# M5R_I2C_MUX.net
KiCad netlist of a schematic drawn in EAGLE
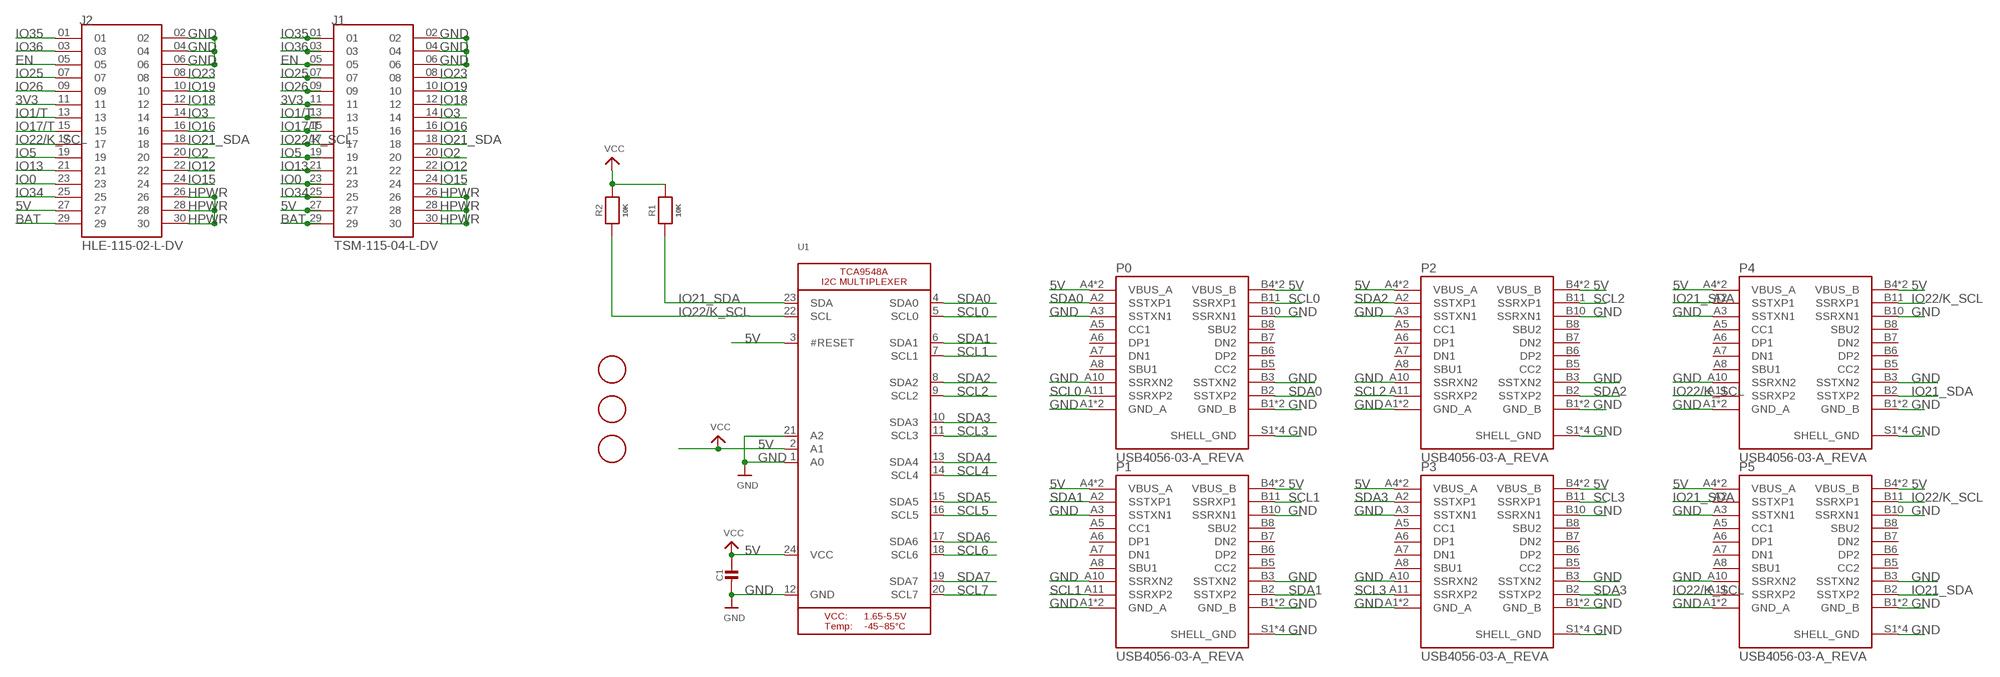
[diagram p0: schematic, sheet 1]

(export (version "E")
  (design (tool "Eeschema 10.0.6"))
  (components
    (comp (ref "C1")
      (value "CAP_CERAMIC0805-NOOUTLINE")
      (footprint "eagle-import:0805-NO")
      (libsource (lib "eagle-import") (part "CAP_CERAMIC0805-NOOUTLINE"))
    )
    (comp (ref "J1")
      (value "TSM-115-04-L-DV")
      (footprint "eagle-import:SAMTEC_TSM-115-04-L-DV")
      (fields (field (name "MF") "Samtec"))
      (libsource (lib "eagle-import") (part "TSM-115-04-L-DV"))
    )
    (comp (ref "J2")
      (value "HLE-115-02-L-DV")
      (footprint "eagle-import:SAMTEC_HLE-115-02-L-DV")
      (fields (field (name "MANUFACTURER") "Samtec Inc."))
      (libsource (lib "eagle-import") (part "HLE-115-02-L-DV"))
    )
    (comp (ref "P0")
      (value "USB4056-03-A_REVA")
      (footprint "eagle-import:GCT_USB4056-03-A_REVA")
      (fields (field (name "MANUFACTURER") "GCT"))
      (libsource (lib "eagle-import") (part "USB4056-03-A_REVA"))
    )
    (comp (ref "P1")
      (value "USB4056-03-A_REVA")
      (footprint "eagle-import:GCT_USB4056-03-A_REVA")
      (fields (field (name "MANUFACTURER") "GCT"))
      (libsource (lib "eagle-import") (part "USB4056-03-A_REVA"))
    )
    (comp (ref "P2")
      (value "USB4056-03-A_REVA")
      (footprint "eagle-import:GCT_USB4056-03-A_REVA")
      (fields (field (name "MANUFACTURER") "GCT"))
      (libsource (lib "eagle-import") (part "USB4056-03-A_REVA"))
    )
    (comp (ref "P3")
      (value "USB4056-03-A_REVA")
      (footprint "eagle-import:GCT_USB4056-03-A_REVA")
      (fields (field (name "MANUFACTURER") "GCT"))
      (libsource (lib "eagle-import") (part "USB4056-03-A_REVA"))
    )
    (comp (ref "P4")
      (value "USB4056-03-A_REVA")
      (footprint "eagle-import:GCT_USB4056-03-A_REVA")
      (fields (field (name "MANUFACTURER") "GCT"))
      (libsource (lib "eagle-import") (part "USB4056-03-A_REVA"))
    )
    (comp (ref "P5")
      (value "USB4056-03-A_REVA")
      (footprint "eagle-import:GCT_USB4056-03-A_REVA")
      (fields (field (name "MANUFACTURER") "GCT"))
      (libsource (lib "eagle-import") (part "USB4056-03-A_REVA"))
    )
    (comp (ref "R1")
      (value "10K")
      (footprint "eagle-import:0805")
      (libsource (lib "eagle-import") (part "RESISTOR_0805"))
    )
    (comp (ref "R2")
      (value "10K")
      (footprint "eagle-import:0805")
      (libsource (lib "eagle-import") (part "RESISTOR_0805"))
    )
    (comp (ref "U$3")
      (value "FIDUCIAL")
      (footprint "eagle-import:FIDUCIAL_1MM")
      (libsource (lib "eagle-import") (part "FIDUCIAL"))
    )
    (comp (ref "U$4")
      (value "FIDUCIAL")
      (footprint "eagle-import:FIDUCIAL_1MM")
      (libsource (lib "eagle-import") (part "FIDUCIAL"))
    )
    (comp (ref "U$5")
      (value "FIDUCIAL")
      (footprint "eagle-import:FIDUCIAL_1MM")
      (libsource (lib "eagle-import") (part "FIDUCIAL"))
    )
    (comp (ref "U1")
      (value "TCA9548A")
      (footprint "eagle-import:TSSOP24")
      (libsource (lib "eagle-import") (part "TCA9548A"))
    )
  )
  (nets
    (net (code "1") (name "/3V3") (class "Default")
      (node (ref "J1") (pin "11") (pinfunction "11_11") (pintype "passive"))
      (node (ref "J2") (pin "11") (pinfunction "11_11") (pintype "passive"))
    )
    (net (code "2") (name "/BAT") (class "Default")
      (node (ref "J1") (pin "29") (pinfunction "29_29") (pintype "passive"))
      (node (ref "J2") (pin "29") (pinfunction "29_29") (pintype "passive"))
    )
    (net (code "3") (name "/EN") (class "Default")
      (node (ref "J1") (pin "05") (pinfunction "05_05") (pintype "passive"))
      (node (ref "J2") (pin "05") (pinfunction "05_05") (pintype "passive"))
    )
    (net (code "4") (name "/HPWR") (class "Default")
      (node (ref "J1") (pin "26") (pinfunction "26_26") (pintype "passive"))
      (node (ref "J1") (pin "28") (pinfunction "28_28") (pintype "passive"))
      (node (ref "J1") (pin "30") (pinfunction "30_30") (pintype "passive"))
      (node (ref "J2") (pin "26") (pinfunction "26_26") (pintype "passive"))
      (node (ref "J2") (pin "28") (pinfunction "28_28") (pintype "passive"))
      (node (ref "J2") (pin "30") (pinfunction "30_30") (pintype "passive"))
    )
    (net (code "5") (name "/IO0") (class "Default")
      (node (ref "J1") (pin "23") (pinfunction "23_23") (pintype "passive"))
      (node (ref "J2") (pin "23") (pinfunction "23_23") (pintype "passive"))
    )
    (net (code "6") (name "/IO1{slash}T") (class "Default")
      (node (ref "J1") (pin "13") (pinfunction "13_13") (pintype "passive"))
      (node (ref "J2") (pin "13") (pinfunction "13_13") (pintype "passive"))
    )
    (net (code "7") (name "/IO2") (class "Default")
      (node (ref "J1") (pin "20") (pinfunction "20_20") (pintype "passive"))
      (node (ref "J2") (pin "20") (pinfunction "20_20") (pintype "passive"))
    )
    (net (code "8") (name "/IO3") (class "Default")
      (node (ref "J1") (pin "14") (pinfunction "14_14") (pintype "passive"))
      (node (ref "J2") (pin "14") (pinfunction "14_14") (pintype "passive"))
    )
    (net (code "9") (name "/IO5") (class "Default")
      (node (ref "J1") (pin "19") (pinfunction "19_19") (pintype "passive"))
      (node (ref "J2") (pin "19") (pinfunction "19_19") (pintype "passive"))
    )
    (net (code "10") (name "/IO12") (class "Default")
      (node (ref "J1") (pin "22") (pinfunction "22_22") (pintype "passive"))
      (node (ref "J2") (pin "22") (pinfunction "22_22") (pintype "passive"))
    )
    (net (code "11") (name "/IO13") (class "Default")
      (node (ref "J1") (pin "21") (pinfunction "21_21") (pintype "passive"))
      (node (ref "J2") (pin "21") (pinfunction "21_21") (pintype "passive"))
    )
    (net (code "12") (name "/IO15") (class "Default")
      (node (ref "J1") (pin "24") (pinfunction "24_24") (pintype "passive"))
      (node (ref "J2") (pin "24") (pinfunction "24_24") (pintype "passive"))
    )
    (net (code "13") (name "/IO16") (class "Default")
      (node (ref "J1") (pin "16") (pinfunction "16_16") (pintype "passive"))
      (node (ref "J2") (pin "16") (pinfunction "16_16") (pintype "passive"))
    )
    (net (code "14") (name "/IO17{slash}T") (class "Default")
      (node (ref "J1") (pin "15") (pinfunction "15_15") (pintype "passive"))
      (node (ref "J2") (pin "15") (pinfunction "15_15") (pintype "passive"))
    )
    (net (code "15") (name "/IO18") (class "Default")
      (node (ref "J1") (pin "12") (pinfunction "12_12") (pintype "passive"))
      (node (ref "J2") (pin "12") (pinfunction "12_12") (pintype "passive"))
    )
    (net (code "16") (name "/IO19") (class "Default")
      (node (ref "J1") (pin "10") (pinfunction "10_10") (pintype "passive"))
      (node (ref "J2") (pin "10") (pinfunction "10_10") (pintype "passive"))
    )
    (net (code "17") (name "/IO21_SDA") (class "Default")
      (node (ref "J1") (pin "18") (pinfunction "18_18") (pintype "passive"))
      (node (ref "J2") (pin "18") (pinfunction "18_18") (pintype "passive"))
      (node (ref "P4") (pin "A2") (pinfunction "SSTXP1_A2") (pintype "bidirectional"))
      (node (ref "P4") (pin "B2") (pinfunction "SSTXP2_B2") (pintype "bidirectional"))
      (node (ref "P5") (pin "A2") (pinfunction "SSTXP1_A2") (pintype "bidirectional"))
      (node (ref "P5") (pin "B2") (pinfunction "SSTXP2_B2") (pintype "bidirectional"))
      (node (ref "R1") (pin "1") (pinfunction "1_1") (pintype "passive"))
      (node (ref "U1") (pin "23") (pinfunction "SDA_23") (pintype "bidirectional"))
    )
    (net (code "18") (name "/IO22{slash}K_SCL") (class "Default")
      (node (ref "J1") (pin "17") (pinfunction "17_17") (pintype "passive"))
      (node (ref "J2") (pin "17") (pinfunction "17_17") (pintype "passive"))
      (node (ref "P4") (pin "A11") (pinfunction "SSRXP2_A11") (pintype "bidirectional"))
      (node (ref "P4") (pin "B11") (pinfunction "SSRXP1_B11") (pintype "bidirectional"))
      (node (ref "P5") (pin "A11") (pinfunction "SSRXP2_A11") (pintype "bidirectional"))
      (node (ref "P5") (pin "B11") (pinfunction "SSRXP1_B11") (pintype "bidirectional"))
      (node (ref "R2") (pin "1") (pinfunction "1_1") (pintype "passive"))
      (node (ref "U1") (pin "22") (pinfunction "SCL_22") (pintype "bidirectional"))
    )
    (net (code "19") (name "/IO23") (class "Default")
      (node (ref "J1") (pin "08") (pinfunction "08_08") (pintype "passive"))
      (node (ref "J2") (pin "08") (pinfunction "08_08") (pintype "passive"))
    )
    (net (code "20") (name "/IO25") (class "Default")
      (node (ref "J1") (pin "07") (pinfunction "07_07") (pintype "passive"))
      (node (ref "J2") (pin "07") (pinfunction "07_07") (pintype "passive"))
    )
    (net (code "21") (name "/IO26") (class "Default")
      (node (ref "J1") (pin "09") (pinfunction "09_09") (pintype "passive"))
      (node (ref "J2") (pin "09") (pinfunction "09_09") (pintype "passive"))
    )
    (net (code "22") (name "/IO34") (class "Default")
      (node (ref "J1") (pin "25") (pinfunction "25_25") (pintype "passive"))
      (node (ref "J2") (pin "25") (pinfunction "25_25") (pintype "passive"))
    )
    (net (code "23") (name "/IO35") (class "Default")
      (node (ref "J1") (pin "01") (pinfunction "01_01") (pintype "passive"))
      (node (ref "J2") (pin "01") (pinfunction "01_01") (pintype "passive"))
    )
    (net (code "24") (name "/IO36") (class "Default")
      (node (ref "J1") (pin "03") (pinfunction "03_03") (pintype "passive"))
      (node (ref "J2") (pin "03") (pinfunction "03_03") (pintype "passive"))
    )
    (net (code "25") (name "/SCL0") (class "Default")
      (node (ref "P0") (pin "A11") (pinfunction "SSRXP2_A11") (pintype "bidirectional"))
      (node (ref "P0") (pin "B11") (pinfunction "SSRXP1_B11") (pintype "bidirectional"))
      (node (ref "U1") (pin "5") (pinfunction "SCL0_5") (pintype "bidirectional"))
    )
    (net (code "26") (name "/SCL1") (class "Default")
      (node (ref "P1") (pin "A11") (pinfunction "SSRXP2_A11") (pintype "bidirectional"))
      (node (ref "P1") (pin "B11") (pinfunction "SSRXP1_B11") (pintype "bidirectional"))
      (node (ref "U1") (pin "7") (pinfunction "SCL1_7") (pintype "bidirectional"))
    )
    (net (code "27") (name "/SCL2") (class "Default")
      (node (ref "P2") (pin "A11") (pinfunction "SSRXP2_A11") (pintype "bidirectional"))
      (node (ref "P2") (pin "B11") (pinfunction "SSRXP1_B11") (pintype "bidirectional"))
      (node (ref "U1") (pin "9") (pinfunction "SCL2_9") (pintype "bidirectional"))
    )
    (net (code "28") (name "/SCL3") (class "Default")
      (node (ref "P3") (pin "A11") (pinfunction "SSRXP2_A11") (pintype "bidirectional"))
      (node (ref "P3") (pin "B11") (pinfunction "SSRXP1_B11") (pintype "bidirectional"))
      (node (ref "U1") (pin "11") (pinfunction "SCL3_11") (pintype "bidirectional"))
    )
    (net (code "29") (name "/SCL4") (class "Default")
      (node (ref "U1") (pin "14") (pinfunction "SCL4_14") (pintype "bidirectional"))
    )
    (net (code "30") (name "/SCL5") (class "Default")
      (node (ref "U1") (pin "16") (pinfunction "SCL5_16") (pintype "bidirectional"))
    )
    (net (code "31") (name "/SCL6") (class "Default")
      (node (ref "U1") (pin "18") (pinfunction "SCL6_18") (pintype "bidirectional"))
    )
    (net (code "32") (name "/SCL7") (class "Default")
      (node (ref "U1") (pin "20") (pinfunction "SCL7_20") (pintype "bidirectional"))
    )
    (net (code "33") (name "/SDA0") (class "Default")
      (node (ref "P0") (pin "A2") (pinfunction "SSTXP1_A2") (pintype "bidirectional"))
      (node (ref "P0") (pin "B2") (pinfunction "SSTXP2_B2") (pintype "bidirectional"))
      (node (ref "U1") (pin "4") (pinfunction "SDA0_4") (pintype "bidirectional"))
    )
    (net (code "34") (name "/SDA1") (class "Default")
      (node (ref "P1") (pin "A2") (pinfunction "SSTXP1_A2") (pintype "bidirectional"))
      (node (ref "P1") (pin "B2") (pinfunction "SSTXP2_B2") (pintype "bidirectional"))
      (node (ref "U1") (pin "6") (pinfunction "SDA1_6") (pintype "bidirectional"))
    )
    (net (code "35") (name "/SDA2") (class "Default")
      (node (ref "P2") (pin "A2") (pinfunction "SSTXP1_A2") (pintype "bidirectional"))
      (node (ref "P2") (pin "B2") (pinfunction "SSTXP2_B2") (pintype "bidirectional"))
      (node (ref "U1") (pin "8") (pinfunction "SDA2_8") (pintype "bidirectional"))
    )
    (net (code "36") (name "/SDA3") (class "Default")
      (node (ref "P3") (pin "A2") (pinfunction "SSTXP1_A2") (pintype "bidirectional"))
      (node (ref "P3") (pin "B2") (pinfunction "SSTXP2_B2") (pintype "bidirectional"))
      (node (ref "U1") (pin "10") (pinfunction "SDA3_10") (pintype "bidirectional"))
    )
    (net (code "37") (name "/SDA4") (class "Default")
      (node (ref "U1") (pin "13") (pinfunction "SDA4_13") (pintype "bidirectional"))
    )
    (net (code "38") (name "/SDA5") (class "Default")
      (node (ref "U1") (pin "15") (pinfunction "SDA5_15") (pintype "bidirectional"))
    )
    (net (code "39") (name "/SDA6") (class "Default")
      (node (ref "U1") (pin "17") (pinfunction "SDA6_17") (pintype "bidirectional"))
    )
    (net (code "40") (name "/SDA7") (class "Default")
      (node (ref "U1") (pin "19") (pinfunction "SDA7_19") (pintype "bidirectional"))
    )
    (net (code "41") (name "GND") (class "Default")
      (node (ref "C1") (pin "2") (pinfunction "2_2") (pintype "passive"))
      (node (ref "J1") (pin "02") (pinfunction "02_02") (pintype "passive"))
      (node (ref "J1") (pin "04") (pinfunction "04_04") (pintype "passive"))
      (node (ref "J1") (pin "06") (pinfunction "06_06") (pintype "passive"))
      (node (ref "J2") (pin "02") (pinfunction "02_02") (pintype "passive"))
      (node (ref "J2") (pin "04") (pinfunction "04_04") (pintype "passive"))
      (node (ref "J2") (pin "06") (pinfunction "06_06") (pintype "passive"))
      (node (ref "P0") (pin "A1") (pinfunction "GND_A_A1") (pintype "power_in"))
      (node (ref "P0") (pin "A10") (pinfunction "SSRXN2_A10") (pintype "bidirectional"))
      (node (ref "P0") (pin "A12") (pinfunction "GND_A_A12") (pintype "power_in"))
      (node (ref "P0") (pin "A3") (pinfunction "SSTXN1_A3") (pintype "bidirectional"))
      (node (ref "P0") (pin "B1") (pinfunction "GND_B_B1") (pintype "power_in"))
      (node (ref "P0") (pin "B10") (pinfunction "SSRXN1_B10") (pintype "bidirectional"))
      (node (ref "P0") (pin "B12") (pinfunction "GND_B_B12") (pintype "power_in"))
      (node (ref "P0") (pin "B3") (pinfunction "SSTXN2_B3") (pintype "bidirectional"))
      (node (ref "P0") (pin "S1") (pinfunction "SHELL_GND_S1") (pintype "power_in"))
      (node (ref "P0") (pin "S2") (pinfunction "SHELL_GND_S2") (pintype "power_in"))
      (node (ref "P0") (pin "S3") (pinfunction "SHELL_GND_S3") (pintype "power_in"))
      (node (ref "P0") (pin "S4") (pinfunction "SHELL_GND_S4") (pintype "power_in"))
      (node (ref "P1") (pin "A1") (pinfunction "GND_A_A1") (pintype "power_in"))
      (node (ref "P1") (pin "A10") (pinfunction "SSRXN2_A10") (pintype "bidirectional"))
      (node (ref "P1") (pin "A12") (pinfunction "GND_A_A12") (pintype "power_in"))
      (node (ref "P1") (pin "A3") (pinfunction "SSTXN1_A3") (pintype "bidirectional"))
      (node (ref "P1") (pin "B1") (pinfunction "GND_B_B1") (pintype "power_in"))
      (node (ref "P1") (pin "B10") (pinfunction "SSRXN1_B10") (pintype "bidirectional"))
      (node (ref "P1") (pin "B12") (pinfunction "GND_B_B12") (pintype "power_in"))
      (node (ref "P1") (pin "B3") (pinfunction "SSTXN2_B3") (pintype "bidirectional"))
      (node (ref "P1") (pin "S1") (pinfunction "SHELL_GND_S1") (pintype "power_in"))
      (node (ref "P1") (pin "S2") (pinfunction "SHELL_GND_S2") (pintype "power_in"))
      (node (ref "P1") (pin "S3") (pinfunction "SHELL_GND_S3") (pintype "power_in"))
      (node (ref "P1") (pin "S4") (pinfunction "SHELL_GND_S4") (pintype "power_in"))
      (node (ref "P2") (pin "A1") (pinfunction "GND_A_A1") (pintype "power_in"))
      (node (ref "P2") (pin "A10") (pinfunction "SSRXN2_A10") (pintype "bidirectional"))
      (node (ref "P2") (pin "A12") (pinfunction "GND_A_A12") (pintype "power_in"))
      (node (ref "P2") (pin "A3") (pinfunction "SSTXN1_A3") (pintype "bidirectional"))
      (node (ref "P2") (pin "B1") (pinfunction "GND_B_B1") (pintype "power_in"))
      (node (ref "P2") (pin "B10") (pinfunction "SSRXN1_B10") (pintype "bidirectional"))
      (node (ref "P2") (pin "B12") (pinfunction "GND_B_B12") (pintype "power_in"))
      (node (ref "P2") (pin "B3") (pinfunction "SSTXN2_B3") (pintype "bidirectional"))
      (node (ref "P2") (pin "S1") (pinfunction "SHELL_GND_S1") (pintype "power_in"))
      (node (ref "P2") (pin "S2") (pinfunction "SHELL_GND_S2") (pintype "power_in"))
      (node (ref "P2") (pin "S3") (pinfunction "SHELL_GND_S3") (pintype "power_in"))
      (node (ref "P2") (pin "S4") (pinfunction "SHELL_GND_S4") (pintype "power_in"))
      (node (ref "P3") (pin "A1") (pinfunction "GND_A_A1") (pintype "power_in"))
      (node (ref "P3") (pin "A10") (pinfunction "SSRXN2_A10") (pintype "bidirectional"))
      (node (ref "P3") (pin "A12") (pinfunction "GND_A_A12") (pintype "power_in"))
      (node (ref "P3") (pin "A3") (pinfunction "SSTXN1_A3") (pintype "bidirectional"))
      (node (ref "P3") (pin "B1") (pinfunction "GND_B_B1") (pintype "power_in"))
      (node (ref "P3") (pin "B10") (pinfunction "SSRXN1_B10") (pintype "bidirectional"))
      (node (ref "P3") (pin "B12") (pinfunction "GND_B_B12") (pintype "power_in"))
      (node (ref "P3") (pin "B3") (pinfunction "SSTXN2_B3") (pintype "bidirectional"))
      (node (ref "P3") (pin "S1") (pinfunction "SHELL_GND_S1") (pintype "power_in"))
      (node (ref "P3") (pin "S2") (pinfunction "SHELL_GND_S2") (pintype "power_in"))
      (node (ref "P3") (pin "S3") (pinfunction "SHELL_GND_S3") (pintype "power_in"))
      (node (ref "P3") (pin "S4") (pinfunction "SHELL_GND_S4") (pintype "power_in"))
      (node (ref "P4") (pin "A1") (pinfunction "GND_A_A1") (pintype "power_in"))
      (node (ref "P4") (pin "A10") (pinfunction "SSRXN2_A10") (pintype "bidirectional"))
      (node (ref "P4") (pin "A12") (pinfunction "GND_A_A12") (pintype "power_in"))
      (node (ref "P4") (pin "A3") (pinfunction "SSTXN1_A3") (pintype "bidirectional"))
      (node (ref "P4") (pin "B1") (pinfunction "GND_B_B1") (pintype "power_in"))
      (node (ref "P4") (pin "B10") (pinfunction "SSRXN1_B10") (pintype "bidirectional"))
      (node (ref "P4") (pin "B12") (pinfunction "GND_B_B12") (pintype "power_in"))
      (node (ref "P4") (pin "B3") (pinfunction "SSTXN2_B3") (pintype "bidirectional"))
      (node (ref "P4") (pin "S1") (pinfunction "SHELL_GND_S1") (pintype "power_in"))
      (node (ref "P4") (pin "S2") (pinfunction "SHELL_GND_S2") (pintype "power_in"))
      (node (ref "P4") (pin "S3") (pinfunction "SHELL_GND_S3") (pintype "power_in"))
      (node (ref "P4") (pin "S4") (pinfunction "SHELL_GND_S4") (pintype "power_in"))
      (node (ref "P5") (pin "A1") (pinfunction "GND_A_A1") (pintype "power_in"))
      (node (ref "P5") (pin "A10") (pinfunction "SSRXN2_A10") (pintype "bidirectional"))
      (node (ref "P5") (pin "A12") (pinfunction "GND_A_A12") (pintype "power_in"))
      (node (ref "P5") (pin "A3") (pinfunction "SSTXN1_A3") (pintype "bidirectional"))
      (node (ref "P5") (pin "B1") (pinfunction "GND_B_B1") (pintype "power_in"))
      (node (ref "P5") (pin "B10") (pinfunction "SSRXN1_B10") (pintype "bidirectional"))
      (node (ref "P5") (pin "B12") (pinfunction "GND_B_B12") (pintype "power_in"))
      (node (ref "P5") (pin "B3") (pinfunction "SSTXN2_B3") (pintype "bidirectional"))
      (node (ref "P5") (pin "S1") (pinfunction "SHELL_GND_S1") (pintype "power_in"))
      (node (ref "P5") (pin "S2") (pinfunction "SHELL_GND_S2") (pintype "power_in"))
      (node (ref "P5") (pin "S3") (pinfunction "SHELL_GND_S3") (pintype "power_in"))
      (node (ref "P5") (pin "S4") (pinfunction "SHELL_GND_S4") (pintype "power_in"))
      (node (ref "U1") (pin "1") (pinfunction "A0_1") (pintype "bidirectional"))
      (node (ref "U1") (pin "12") (pinfunction "GND_12") (pintype "bidirectional"))
      (node (ref "U1") (pin "21") (pinfunction "A2_21") (pintype "bidirectional"))
    )
    (net (code "42") (name "VCC") (class "Default")
      (node (ref "C1") (pin "1") (pinfunction "1_1") (pintype "passive"))
      (node (ref "J1") (pin "27") (pinfunction "27_27") (pintype "passive"))
      (node (ref "J2") (pin "27") (pinfunction "27_27") (pintype "passive"))
      (node (ref "P0") (pin "A4") (pinfunction "VBUS_A_A4") (pintype "power_in"))
      (node (ref "P0") (pin "A9") (pinfunction "VBUS_A_A9") (pintype "power_in"))
      (node (ref "P0") (pin "B4") (pinfunction "VBUS_B_B4") (pintype "power_in"))
      (node (ref "P0") (pin "B9") (pinfunction "VBUS_B_B9") (pintype "power_in"))
      (node (ref "P1") (pin "A4") (pinfunction "VBUS_A_A4") (pintype "power_in"))
      (node (ref "P1") (pin "A9") (pinfunction "VBUS_A_A9") (pintype "power_in"))
      (node (ref "P1") (pin "B4") (pinfunction "VBUS_B_B4") (pintype "power_in"))
      (node (ref "P1") (pin "B9") (pinfunction "VBUS_B_B9") (pintype "power_in"))
      (node (ref "P2") (pin "A4") (pinfunction "VBUS_A_A4") (pintype "power_in"))
      (node (ref "P2") (pin "A9") (pinfunction "VBUS_A_A9") (pintype "power_in"))
      (node (ref "P2") (pin "B4") (pinfunction "VBUS_B_B4") (pintype "power_in"))
      (node (ref "P2") (pin "B9") (pinfunction "VBUS_B_B9") (pintype "power_in"))
      (node (ref "P3") (pin "A4") (pinfunction "VBUS_A_A4") (pintype "power_in"))
      (node (ref "P3") (pin "A9") (pinfunction "VBUS_A_A9") (pintype "power_in"))
      (node (ref "P3") (pin "B4") (pinfunction "VBUS_B_B4") (pintype "power_in"))
      (node (ref "P3") (pin "B9") (pinfunction "VBUS_B_B9") (pintype "power_in"))
      (node (ref "P4") (pin "A4") (pinfunction "VBUS_A_A4") (pintype "power_in"))
      (node (ref "P4") (pin "A9") (pinfunction "VBUS_A_A9") (pintype "power_in"))
      (node (ref "P4") (pin "B4") (pinfunction "VBUS_B_B4") (pintype "power_in"))
      (node (ref "P4") (pin "B9") (pinfunction "VBUS_B_B9") (pintype "power_in"))
      (node (ref "P5") (pin "A4") (pinfunction "VBUS_A_A4") (pintype "power_in"))
      (node (ref "P5") (pin "A9") (pinfunction "VBUS_A_A9") (pintype "power_in"))
      (node (ref "P5") (pin "B4") (pinfunction "VBUS_B_B4") (pintype "power_in"))
      (node (ref "P5") (pin "B9") (pinfunction "VBUS_B_B9") (pintype "power_in"))
      (node (ref "R1") (pin "2") (pinfunction "2_2") (pintype "passive"))
      (node (ref "R2") (pin "2") (pinfunction "2_2") (pintype "passive"))
      (node (ref "U1") (pin "2") (pinfunction "A1_2") (pintype "bidirectional"))
      (node (ref "U1") (pin "24") (pinfunction "VCC_24") (pintype "bidirectional"))
      (node (ref "U1") (pin "3") (pinfunction "#RESET_3") (pintype "bidirectional"))
    )
    (net (code "43") (name "unconnected-(P0-CC1-PadA5)") (class "Default")
      (node (ref "P0") (pin "A5") (pinfunction "CC1_A5") (pintype "bidirectional"))
    )
    (net (code "44") (name "unconnected-(P0-CC2-PadB5)") (class "Default")
      (node (ref "P0") (pin "B5") (pinfunction "CC2_B5") (pintype "bidirectional"))
    )
    (net (code "45") (name "unconnected-(P0-DN1-PadA7)") (class "Default")
      (node (ref "P0") (pin "A7") (pinfunction "DN1_A7") (pintype "bidirectional"))
    )
    (net (code "46") (name "unconnected-(P0-DN2-PadB7)") (class "Default")
      (node (ref "P0") (pin "B7") (pinfunction "DN2_B7") (pintype "bidirectional"))
    )
    (net (code "47") (name "unconnected-(P0-DP1-PadA6)") (class "Default")
      (node (ref "P0") (pin "A6") (pinfunction "DP1_A6") (pintype "bidirectional"))
    )
    (net (code "48") (name "unconnected-(P0-DP2-PadB6)") (class "Default")
      (node (ref "P0") (pin "B6") (pinfunction "DP2_B6") (pintype "bidirectional"))
    )
    (net (code "49") (name "unconnected-(P0-SBU1-PadA8)") (class "Default")
      (node (ref "P0") (pin "A8") (pinfunction "SBU1_A8") (pintype "bidirectional"))
    )
    (net (code "50") (name "unconnected-(P0-SBU2-PadB8)") (class "Default")
      (node (ref "P0") (pin "B8") (pinfunction "SBU2_B8") (pintype "bidirectional"))
    )
    (net (code "51") (name "unconnected-(P1-CC1-PadA5)") (class "Default")
      (node (ref "P1") (pin "A5") (pinfunction "CC1_A5") (pintype "bidirectional"))
    )
    (net (code "52") (name "unconnected-(P1-CC2-PadB5)") (class "Default")
      (node (ref "P1") (pin "B5") (pinfunction "CC2_B5") (pintype "bidirectional"))
    )
    (net (code "53") (name "unconnected-(P1-DN1-PadA7)") (class "Default")
      (node (ref "P1") (pin "A7") (pinfunction "DN1_A7") (pintype "bidirectional"))
    )
    (net (code "54") (name "unconnected-(P1-DN2-PadB7)") (class "Default")
      (node (ref "P1") (pin "B7") (pinfunction "DN2_B7") (pintype "bidirectional"))
    )
    (net (code "55") (name "unconnected-(P1-DP1-PadA6)") (class "Default")
      (node (ref "P1") (pin "A6") (pinfunction "DP1_A6") (pintype "bidirectional"))
    )
    (net (code "56") (name "unconnected-(P1-DP2-PadB6)") (class "Default")
      (node (ref "P1") (pin "B6") (pinfunction "DP2_B6") (pintype "bidirectional"))
    )
    (net (code "57") (name "unconnected-(P1-SBU1-PadA8)") (class "Default")
      (node (ref "P1") (pin "A8") (pinfunction "SBU1_A8") (pintype "bidirectional"))
    )
    (net (code "58") (name "unconnected-(P1-SBU2-PadB8)") (class "Default")
      (node (ref "P1") (pin "B8") (pinfunction "SBU2_B8") (pintype "bidirectional"))
    )
    (net (code "59") (name "unconnected-(P2-CC1-PadA5)") (class "Default")
      (node (ref "P2") (pin "A5") (pinfunction "CC1_A5") (pintype "bidirectional"))
    )
    (net (code "60") (name "unconnected-(P2-CC2-PadB5)") (class "Default")
      (node (ref "P2") (pin "B5") (pinfunction "CC2_B5") (pintype "bidirectional"))
    )
    (net (code "61") (name "unconnected-(P2-DN1-PadA7)") (class "Default")
      (node (ref "P2") (pin "A7") (pinfunction "DN1_A7") (pintype "bidirectional"))
    )
    (net (code "62") (name "unconnected-(P2-DN2-PadB7)") (class "Default")
      (node (ref "P2") (pin "B7") (pinfunction "DN2_B7") (pintype "bidirectional"))
    )
    (net (code "63") (name "unconnected-(P2-DP1-PadA6)") (class "Default")
      (node (ref "P2") (pin "A6") (pinfunction "DP1_A6") (pintype "bidirectional"))
    )
    (net (code "64") (name "unconnected-(P2-DP2-PadB6)") (class "Default")
      (node (ref "P2") (pin "B6") (pinfunction "DP2_B6") (pintype "bidirectional"))
    )
    (net (code "65") (name "unconnected-(P2-SBU1-PadA8)") (class "Default")
      (node (ref "P2") (pin "A8") (pinfunction "SBU1_A8") (pintype "bidirectional"))
    )
    (net (code "66") (name "unconnected-(P2-SBU2-PadB8)") (class "Default")
      (node (ref "P2") (pin "B8") (pinfunction "SBU2_B8") (pintype "bidirectional"))
    )
    (net (code "67") (name "unconnected-(P3-CC1-PadA5)") (class "Default")
      (node (ref "P3") (pin "A5") (pinfunction "CC1_A5") (pintype "bidirectional"))
    )
    (net (code "68") (name "unconnected-(P3-CC2-PadB5)") (class "Default")
      (node (ref "P3") (pin "B5") (pinfunction "CC2_B5") (pintype "bidirectional"))
    )
    (net (code "69") (name "unconnected-(P3-DN1-PadA7)") (class "Default")
      (node (ref "P3") (pin "A7") (pinfunction "DN1_A7") (pintype "bidirectional"))
    )
    (net (code "70") (name "unconnected-(P3-DN2-PadB7)") (class "Default")
      (node (ref "P3") (pin "B7") (pinfunction "DN2_B7") (pintype "bidirectional"))
    )
    (net (code "71") (name "unconnected-(P3-DP1-PadA6)") (class "Default")
      (node (ref "P3") (pin "A6") (pinfunction "DP1_A6") (pintype "bidirectional"))
    )
    (net (code "72") (name "unconnected-(P3-DP2-PadB6)") (class "Default")
      (node (ref "P3") (pin "B6") (pinfunction "DP2_B6") (pintype "bidirectional"))
    )
    (net (code "73") (name "unconnected-(P3-SBU1-PadA8)") (class "Default")
      (node (ref "P3") (pin "A8") (pinfunction "SBU1_A8") (pintype "bidirectional"))
    )
    (net (code "74") (name "unconnected-(P3-SBU2-PadB8)") (class "Default")
      (node (ref "P3") (pin "B8") (pinfunction "SBU2_B8") (pintype "bidirectional"))
    )
    (net (code "75") (name "unconnected-(P4-CC1-PadA5)") (class "Default")
      (node (ref "P4") (pin "A5") (pinfunction "CC1_A5") (pintype "bidirectional"))
    )
    (net (code "76") (name "unconnected-(P4-CC2-PadB5)") (class "Default")
      (node (ref "P4") (pin "B5") (pinfunction "CC2_B5") (pintype "bidirectional"))
    )
    (net (code "77") (name "unconnected-(P4-DN1-PadA7)") (class "Default")
      (node (ref "P4") (pin "A7") (pinfunction "DN1_A7") (pintype "bidirectional"))
    )
    (net (code "78") (name "unconnected-(P4-DN2-PadB7)") (class "Default")
      (node (ref "P4") (pin "B7") (pinfunction "DN2_B7") (pintype "bidirectional"))
    )
    (net (code "79") (name "unconnected-(P4-DP1-PadA6)") (class "Default")
      (node (ref "P4") (pin "A6") (pinfunction "DP1_A6") (pintype "bidirectional"))
    )
    (net (code "80") (name "unconnected-(P4-DP2-PadB6)") (class "Default")
      (node (ref "P4") (pin "B6") (pinfunction "DP2_B6") (pintype "bidirectional"))
    )
    (net (code "81") (name "unconnected-(P4-SBU1-PadA8)") (class "Default")
      (node (ref "P4") (pin "A8") (pinfunction "SBU1_A8") (pintype "bidirectional"))
    )
    (net (code "82") (name "unconnected-(P4-SBU2-PadB8)") (class "Default")
      (node (ref "P4") (pin "B8") (pinfunction "SBU2_B8") (pintype "bidirectional"))
    )
    (net (code "83") (name "unconnected-(P5-CC1-PadA5)") (class "Default")
      (node (ref "P5") (pin "A5") (pinfunction "CC1_A5") (pintype "bidirectional"))
    )
    (net (code "84") (name "unconnected-(P5-CC2-PadB5)") (class "Default")
      (node (ref "P5") (pin "B5") (pinfunction "CC2_B5") (pintype "bidirectional"))
    )
    (net (code "85") (name "unconnected-(P5-DN1-PadA7)") (class "Default")
      (node (ref "P5") (pin "A7") (pinfunction "DN1_A7") (pintype "bidirectional"))
    )
    (net (code "86") (name "unconnected-(P5-DN2-PadB7)") (class "Default")
      (node (ref "P5") (pin "B7") (pinfunction "DN2_B7") (pintype "bidirectional"))
    )
    (net (code "87") (name "unconnected-(P5-DP1-PadA6)") (class "Default")
      (node (ref "P5") (pin "A6") (pinfunction "DP1_A6") (pintype "bidirectional"))
    )
    (net (code "88") (name "unconnected-(P5-DP2-PadB6)") (class "Default")
      (node (ref "P5") (pin "B6") (pinfunction "DP2_B6") (pintype "bidirectional"))
    )
    (net (code "89") (name "unconnected-(P5-SBU1-PadA8)") (class "Default")
      (node (ref "P5") (pin "A8") (pinfunction "SBU1_A8") (pintype "bidirectional"))
    )
    (net (code "90") (name "unconnected-(P5-SBU2-PadB8)") (class "Default")
      (node (ref "P5") (pin "B8") (pinfunction "SBU2_B8") (pintype "bidirectional"))
    )
  )
)
